# SparkFun_ESP8266_Thing_V10a.net
KiCad netlist of a schematic drawn in EAGLE
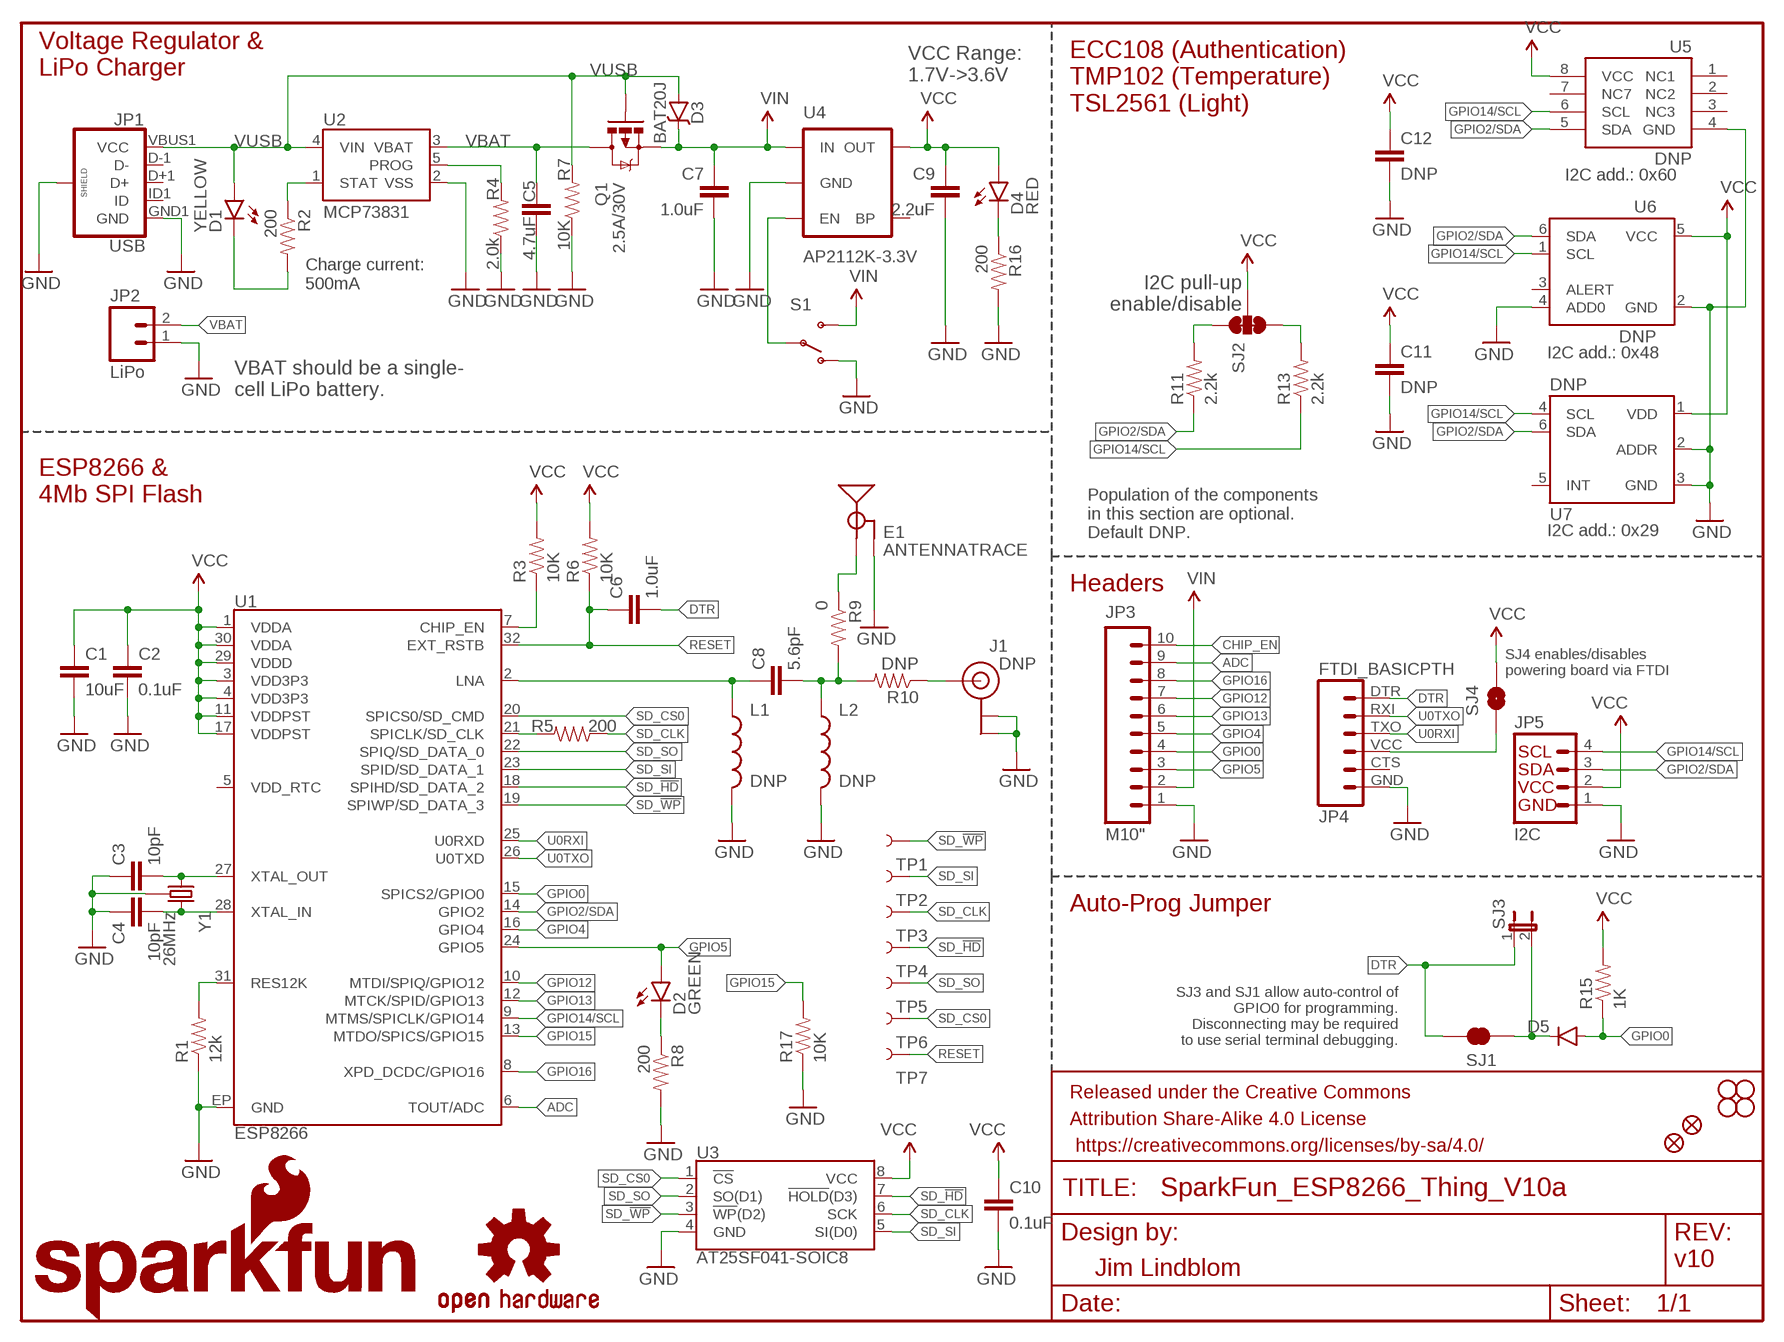
[diagram p0: schematic, sheet 1]

(export (version "E")
  (design (tool "Eeschema 10.0.6"))
  (components
    (comp (ref "C1")
      (value "10uF")
      (footprint "eagle-import:0603-CAP")
      (libsource (lib "eagle-import") (part "10UF-6.3V-20%(0603)"))
    )
    (comp (ref "C2")
      (value "0.1uF")
      (footprint "eagle-import:0603-CAP")
      (libsource (lib "eagle-import") (part "0.1UF-25V(+80/-20%)(0603)"))
    )
    (comp (ref "C3")
      (value "10pF")
      (footprint "eagle-import:0603-CAP")
      (libsource (lib "eagle-import") (part "10PF-50V-5%(0603)"))
    )
    (comp (ref "C4")
      (value "10pF")
      (footprint "eagle-import:0603-CAP")
      (libsource (lib "eagle-import") (part "10PF-50V-5%(0603)"))
    )
    (comp (ref "C5")
      (value "4.7uF")
      (footprint "eagle-import:0603-CAP")
      (libsource (lib "eagle-import") (part "4.7UF-6.3V-10%(0603)0603"))
    )
    (comp (ref "C6")
      (value "1.0uF")
      (footprint "eagle-import:0603-CAP")
      (libsource (lib "eagle-import") (part "1.0UF-16V-10%(0603)"))
    )
    (comp (ref "C7")
      (value "1.0uF")
      (footprint "eagle-import:0805")
      (libsource (lib "eagle-import") (part "1.0UF-25V-+80/-20(0805)"))
    )
    (comp (ref "C8")
      (value "5.6pF")
      (footprint "eagle-import:0603-CAP")
      (libsource (lib "eagle-import") (part "CAP0603-CAP"))
    )
    (comp (ref "C9")
      (value "2.2uF")
      (footprint "eagle-import:0603-CAP")
      (libsource (lib "eagle-import") (part "2.2UF-10V-20%(0603)"))
    )
    (comp (ref "C10")
      (value "0.1uF")
      (footprint "eagle-import:0603-CAP")
      (libsource (lib "eagle-import") (part "0.1UF-25V(+80/-20%)(0603)"))
    )
    (comp (ref "C11")
      (value "DNP")
      (footprint "eagle-import:0603-CAP")
      (libsource (lib "eagle-import") (part "0.1UF-25V(+80/-20%)(0603)"))
    )
    (comp (ref "C12")
      (value "DNP")
      (footprint "eagle-import:0603-CAP")
      (libsource (lib "eagle-import") (part "0.1UF-25V(+80/-20%)(0603)"))
    )
    (comp (ref "D1")
      (value "YELLOW")
      (footprint "eagle-import:LED-0603")
      (libsource (lib "eagle-import") (part "LED-YELLOW0603"))
    )
    (comp (ref "D2")
      (value "GREEN")
      (footprint "eagle-import:LED-0603")
      (libsource (lib "eagle-import") (part "LED-GREEN0603"))
    )
    (comp (ref "D3")
      (value "BAT20J")
      (footprint "eagle-import:SOD-323")
      (libsource (lib "eagle-import") (part "DIODE-SCHOTTKY-BAT20J"))
    )
    (comp (ref "D4")
      (value "RED")
      (footprint "eagle-import:LED-0603")
      (libsource (lib "eagle-import") (part "LED-RED0603"))
    )
    (comp (ref "D5")
      (value "DIODEBAS16")
      (footprint "eagle-import:SOD-323")
      (libsource (lib "eagle-import") (part "DIODEBAS16"))
    )
    (comp (ref "E1")
      (value "ANTENNATRACE")
      (footprint "eagle-import:TRACE_ANTENNA_2.4GHZ_25.7MM")
      (libsource (lib "eagle-import") (part "ANTENNATRACE"))
    )
    (comp (ref "FID1")
      (value "FIDUCIAL1X2")
      (footprint "eagle-import:FIDUCIAL-1X2")
      (libsource (lib "eagle-import") (part "FIDUCIAL1X2"))
    )
    (comp (ref "FID2")
      (value "FIDUCIAL1X2")
      (footprint "eagle-import:FIDUCIAL-1X2")
      (libsource (lib "eagle-import") (part "FIDUCIAL1X2"))
    )
    (comp (ref "FRAME1")
      (value "FRAME-LETTER")
      (footprint "eagle-import:CREATIVE_COMMONS")
      (libsource (lib "eagle-import") (part "FRAME-LETTER"))
    )
    (comp (ref "J1")
      (value "DNP")
      (footprint "eagle-import:U.FL")
      (libsource (lib "eagle-import") (part "U.FL"))
    )
    (comp (ref "JP1")
      (value "USB")
      (footprint "eagle-import:USB-B-MICRO-SMD_V03")
      (libsource (lib "eagle-import") (part "USB_MICROB_PLUGCONN-11752"))
    )
    (comp (ref "JP2")
      (value "LiPo")
      (footprint "eagle-import:JST-2-PTH")
      (libsource (lib "eagle-import") (part "M02JST-PTH-2"))
    )
    (comp (ref "JP3")
      (value "M10\"")
      (footprint "eagle-import:1X10")
      (libsource (lib "eagle-import") (part "M10{dblquote}"))
    )
    (comp (ref "JP4")
      (value "FTDI_BASICPTH")
      (footprint "eagle-import:FTDI_BASIC")
      (libsource (lib "eagle-import") (part "FTDI_BASICPTH"))
    )
    (comp (ref "JP5")
      (value "I2C")
      (footprint "eagle-import:1X04")
      (libsource (lib "eagle-import") (part "I2C_STANDARD"))
    )
    (comp (ref "L1")
      (value "DNP")
      (footprint "eagle-import:0603")
      (libsource (lib "eagle-import") (part "INDUCTOR0603"))
    )
    (comp (ref "L2")
      (value "DNP")
      (footprint "eagle-import:0603")
      (libsource (lib "eagle-import") (part "INDUCTOR0603"))
    )
    (comp (ref "LOGO1")
      (value "SFE_LOGO_NAME.2_INCH")
      (footprint "eagle-import:SFE_LOGO_NAME_.2")
      (libsource (lib "eagle-import") (part "SFE_LOGO_NAME.2_INCH"))
    )
    (comp (ref "LOGO3")
      (value "SFE_LOGO_FLAME.1_INCH")
      (footprint "eagle-import:SFE_LOGO_FLAME_.1")
      (libsource (lib "eagle-import") (part "SFE_LOGO_FLAME.1_INCH"))
    )
    (comp (ref "LOGO4")
      (value "OSHW-LOGOS")
      (footprint "eagle-import:OSHW-LOGO-S")
      (libsource (lib "eagle-import") (part "OSHW-LOGOS"))
    )
    (comp (ref "Q1")
      (value "2.5A/30V")
      (footprint "eagle-import:SOT23-3")
      (libsource (lib "eagle-import") (part "MOSFET-PCHANNELDMG2307L"))
    )
    (comp (ref "R1")
      (value "12k")
      (footprint "eagle-import:0603-RES")
      (libsource (lib "eagle-import") (part "12KOHM-1/10W-1%(0603)"))
    )
    (comp (ref "R2")
      (value "200")
      (footprint "eagle-import:0603-RES")
      (libsource (lib "eagle-import") (part "200OHM1/10W1%(0603)"))
    )
    (comp (ref "R3")
      (value "10K")
      (footprint "eagle-import:0603-RES")
      (libsource (lib "eagle-import") (part "10KOHM1/10W1%(0603)0603"))
    )
    (comp (ref "R4")
      (value "2.0k")
      (footprint "eagle-import:0603-RES")
      (libsource (lib "eagle-import") (part "2.0KOHM1/10W5%(0603)"))
    )
    (comp (ref "R5")
      (value "200")
      (footprint "eagle-import:0603-RES")
      (libsource (lib "eagle-import") (part "200OHM1/10W1%(0603)"))
    )
    (comp (ref "R6")
      (value "10K")
      (footprint "eagle-import:0603-RES")
      (libsource (lib "eagle-import") (part "10KOHM1/10W1%(0603)0603"))
    )
    (comp (ref "R7")
      (value "10K")
      (footprint "eagle-import:0603-RES")
      (libsource (lib "eagle-import") (part "10KOHM1/10W1%(0603)0603"))
    )
    (comp (ref "R8")
      (value "200")
      (footprint "eagle-import:0603-RES")
      (libsource (lib "eagle-import") (part "200OHM1/10W1%(0603)"))
    )
    (comp (ref "R9")
      (value "0")
      (footprint "eagle-import:0603")
      (libsource (lib "eagle-import") (part "0OHM1/10W5%(0603)"))
    )
    (comp (ref "R10")
      (value "DNP")
      (footprint "eagle-import:0603-RES")
      (libsource (lib "eagle-import") (part "RESISTOR0603-RES"))
    )
    (comp (ref "R11")
      (value "2.2k")
      (footprint "eagle-import:0603-RES")
      (libsource (lib "eagle-import") (part "2.2KOHM1/10W1%(0603)"))
    )
    (comp (ref "R13")
      (value "2.2k")
      (footprint "eagle-import:0603-RES")
      (libsource (lib "eagle-import") (part "2.2KOHM1/10W1%(0603)"))
    )
    (comp (ref "R15")
      (value "1K")
      (footprint "eagle-import:0603-RES")
      (libsource (lib "eagle-import") (part "1KOHM1/10W1%(0603)"))
    )
    (comp (ref "R16")
      (value "200")
      (footprint "eagle-import:0603-RES")
      (libsource (lib "eagle-import") (part "200OHM1/10W1%(0603)"))
    )
    (comp (ref "R17")
      (value "10K")
      (footprint "eagle-import:0603-RES")
      (libsource (lib "eagle-import") (part "10KOHM1/10W1%(0603)0603"))
    )
    (comp (ref "S1")
      (value "SWITCH-SPDT-SMD-A")
      (footprint "eagle-import:SWITCH-SPST-SMD-A")
      (libsource (lib "eagle-import") (part "SWITCH-SPDT-SMD-A"))
    )
    (comp (ref "SJ1")
      (value "JUMPER-PAD-2-NC_BY_TRACE")
      (footprint "eagle-import:PAD-JUMPER-2-NC_BY_TRACE_YES_SILK")
      (libsource (lib "eagle-import") (part "JUMPER-PAD-2-NC_BY_TRACE"))
    )
    (comp (ref "SJ2")
      (value "JUMPER-PAD-3-NC_BY_TRACE")
      (footprint "eagle-import:PAD-JUMPER-3-3OF3_NC_BY_TRACE_YES_SILK_FULL_BOX")
      (libsource (lib "eagle-import") (part "JUMPER-PAD-3-NC_BY_TRACE"))
    )
    (comp (ref "SJ3")
      (value "JUMPER-PTH-2-NC")
      (footprint "eagle-import:PTH-JUMPER-NC_BOTTOM_NO_SILK")
      (libsource (lib "eagle-import") (part "JUMPER-PTH-2-NC"))
    )
    (comp (ref "SJ4")
      (value "JUMPER-PAD-2-NOYES_SILK")
      (footprint "eagle-import:PAD-JUMPER-2-NO_YES_SILK")
      (libsource (lib "eagle-import") (part "JUMPER-PAD-2-NOYES_SILK"))
    )
    (comp (ref "STANDOFF1")
      (value "STAND-OFF")
      (footprint "eagle-import:STAND-OFF")
      (libsource (lib "eagle-import") (part "STAND-OFF"))
    )
    (comp (ref "STANDOFF2")
      (value "STAND-OFF")
      (footprint "eagle-import:STAND-OFF")
      (libsource (lib "eagle-import") (part "STAND-OFF"))
    )
    (comp (ref "STANDOFF3")
      (value "STAND-OFF")
      (footprint "eagle-import:STAND-OFF")
      (libsource (lib "eagle-import") (part "STAND-OFF"))
    )
    (comp (ref "STANDOFF4")
      (value "STAND-OFF")
      (footprint "eagle-import:STAND-OFF")
      (libsource (lib "eagle-import") (part "STAND-OFF"))
    )
    (comp (ref "TP1")
      (value "TEST-POINT3X5")
      (footprint "eagle-import:PAD.03X.05")
      (libsource (lib "eagle-import") (part "TEST-POINT3X5"))
    )
    (comp (ref "TP2")
      (value "TEST-POINT3X5")
      (footprint "eagle-import:PAD.03X.05")
      (libsource (lib "eagle-import") (part "TEST-POINT3X5"))
    )
    (comp (ref "TP3")
      (value "TEST-POINT3X5")
      (footprint "eagle-import:PAD.03X.05")
      (libsource (lib "eagle-import") (part "TEST-POINT3X5"))
    )
    (comp (ref "TP4")
      (value "TEST-POINT3X5")
      (footprint "eagle-import:PAD.03X.05")
      (libsource (lib "eagle-import") (part "TEST-POINT3X5"))
    )
    (comp (ref "TP5")
      (value "TEST-POINT3X5")
      (footprint "eagle-import:PAD.03X.05")
      (libsource (lib "eagle-import") (part "TEST-POINT3X5"))
    )
    (comp (ref "TP6")
      (value "TEST-POINT3X5")
      (footprint "eagle-import:PAD.03X.05")
      (libsource (lib "eagle-import") (part "TEST-POINT3X5"))
    )
    (comp (ref "TP7")
      (value "TEST-POINT3X5")
      (footprint "eagle-import:PAD.03X.05")
      (libsource (lib "eagle-import") (part "TEST-POINT3X5"))
    )
    (comp (ref "U1")
      (value "ESP8266")
      (footprint "eagle-import:QFN32")
      (libsource (lib "eagle-import") (part "ESP8266"))
    )
    (comp (ref "U2")
      (value "MCP73831")
      (footprint "eagle-import:SOT23-5")
      (libsource (lib "eagle-import") (part "MCP73831"))
    )
    (comp (ref "U3")
      (value "AT25SF041-SOIC8")
      (footprint "eagle-import:SO08")
      (libsource (lib "eagle-import") (part "AT25SF041-SOIC8"))
    )
    (comp (ref "U4")
      (value "AP2112K-3.3V")
      (footprint "eagle-import:SOT23-5")
      (libsource (lib "eagle-import") (part "V_REG_LDOSMD"))
    )
    (comp (ref "U5")
      (value "DNP")
      (footprint "eagle-import:UDFN8")
      (libsource (lib "eagle-import") (part "ATECC108-MAHDA"))
    )
    (comp (ref "U6")
      (value "DNP")
      (footprint "eagle-import:SOT563-2")
      (libsource (lib "eagle-import") (part "TMP1021{colon}1"))
    )
    (comp (ref "U7")
      (value "DNP")
      (footprint "eagle-import:FN-6")
      (libsource (lib "eagle-import") (part "TSL2561FN"))
    )
    (comp (ref "Y1")
      (value "26MHz")
      (footprint "eagle-import:CRYSTAL-SMD-3.2X2.5")
      (libsource (lib "eagle-import") (part "CRYSTAL-GROUNDED3.2X2.5"))
    )
  )
  (nets
    (net (code "1") (name "/SD_~{HD}") (class "Default")
      (node (ref "TP4") (pin "P$1") (pinfunction "1_P$1") (pintype "bidirectional"))
      (node (ref "U1") (pin "18") (pinfunction "SPIHD/SD_DATA_2_18") (pintype "bidirectional"))
      (node (ref "U3") (pin "7") (pinfunction "~{HOLD}(D3)_7") (pintype "bidirectional"))
    )
    (net (code "2") (name "/SD_~{WP}") (class "Default")
      (node (ref "TP1") (pin "P$1") (pinfunction "1_P$1") (pintype "bidirectional"))
      (node (ref "U1") (pin "19") (pinfunction "SPIWP/SD_DATA_3_19") (pintype "bidirectional"))
      (node (ref "U3") (pin "3") (pinfunction "~{WP}(D2)_3") (pintype "bidirectional"))
    )
    (net (code "3") (name "/VUSB") (class "Default")
      (node (ref "D1") (pin "A") (pinfunction "A_A") (pintype "passive"))
      (node (ref "D3") (pin "A") (pinfunction "A_A") (pintype "passive"))
      (node (ref "JP1") (pin "VBUS1") (pinfunction "VCC_VBUS1") (pintype "bidirectional"))
      (node (ref "Q1") (pin "1") (pinfunction "G_1") (pintype "passive"))
      (node (ref "R7") (pin "2") (pinfunction "2_2") (pintype "passive"))
      (node (ref "U2") (pin "4") (pinfunction "VIN_4") (pintype "power_in"))
    )
    (net (code "4") (name "ADC") (class "Default")
      (node (ref "JP3") (pin "9") (pinfunction "9_9") (pintype "passive"))
      (node (ref "U1") (pin "6") (pinfunction "TOUT/ADC_6") (pintype "bidirectional"))
    )
    (net (code "5") (name "CHIP_EN") (class "Default")
      (node (ref "JP3") (pin "10") (pinfunction "10_10") (pintype "passive"))
      (node (ref "R3") (pin "1") (pinfunction "1_1") (pintype "passive"))
      (node (ref "U1") (pin "7") (pinfunction "CHIP_EN_7") (pintype "bidirectional"))
    )
    (net (code "6") (name "DTR") (class "Default")
      (node (ref "C6") (pin "2") (pinfunction "2_2") (pintype "passive"))
      (node (ref "JP4") (pin "DTR") (pinfunction "1_DTR") (pintype "passive"))
      (node (ref "SJ1") (pin "2") (pinfunction "2_2") (pintype "passive"))
      (node (ref "SJ3") (pin "1") (pinfunction "1_1") (pintype "passive"))
    )
    (net (code "7") (name "GND") (class "Default")
      (node (ref "C1") (pin "2") (pinfunction "2_2") (pintype "passive"))
      (node (ref "C10") (pin "2") (pinfunction "2_2") (pintype "passive"))
      (node (ref "C11") (pin "2") (pinfunction "2_2") (pintype "passive"))
      (node (ref "C12") (pin "2") (pinfunction "2_2") (pintype "passive"))
      (node (ref "C2") (pin "2") (pinfunction "2_2") (pintype "passive"))
      (node (ref "C3") (pin "1") (pinfunction "1_1") (pintype "passive"))
      (node (ref "C4") (pin "1") (pinfunction "1_1") (pintype "passive"))
      (node (ref "C5") (pin "2") (pinfunction "2_2") (pintype "passive"))
      (node (ref "C7") (pin "2") (pinfunction "2_2") (pintype "passive"))
      (node (ref "C9") (pin "2") (pinfunction "2_2") (pintype "passive"))
      (node (ref "E1") (pin "GND") (pinfunction "GND_GND") (pintype "bidirectional"))
      (node (ref "E1") (pin "GND2") (pinfunction "GND_GND2") (pintype "bidirectional"))
      (node (ref "J1") (pin "P$1") (pinfunction "GND_P$1") (pintype "bidirectional"))
      (node (ref "J1") (pin "P$2") (pinfunction "GND_P$2") (pintype "bidirectional"))
      (node (ref "JP1") (pin "GND1") (pinfunction "GND_GND1") (pintype "bidirectional"))
      (node (ref "JP1") (pin "SHIELD1") (pinfunction "SHIELD_SHIELD1") (pintype "bidirectional"))
      (node (ref "JP1") (pin "SHIELD2") (pinfunction "SHIELD_SHIELD2") (pintype "bidirectional"))
      (node (ref "JP1") (pin "SHIELD3") (pinfunction "SHIELD_SHIELD3") (pintype "bidirectional"))
      (node (ref "JP2") (pin "1") (pinfunction "1_1") (pintype "passive"))
      (node (ref "JP3") (pin "1") (pinfunction "1_1") (pintype "passive"))
      (node (ref "JP4") (pin "GND") (pinfunction "6_GND") (pintype "passive"))
      (node (ref "JP5") (pin "1") (pinfunction "1_1") (pintype "passive"))
      (node (ref "L1") (pin "2") (pinfunction "2_2") (pintype "passive"))
      (node (ref "L2") (pin "2") (pinfunction "2_2") (pintype "passive"))
      (node (ref "R1") (pin "1") (pinfunction "1_1") (pintype "passive"))
      (node (ref "R16") (pin "2") (pinfunction "2_2") (pintype "passive"))
      (node (ref "R17") (pin "1") (pinfunction "1_1") (pintype "passive"))
      (node (ref "R4") (pin "1") (pinfunction "1_1") (pintype "passive"))
      (node (ref "R7") (pin "1") (pinfunction "1_1") (pintype "passive"))
      (node (ref "R8") (pin "2") (pinfunction "2_2") (pintype "passive"))
      (node (ref "S1") (pin "1") (pinfunction "O_1") (pintype "passive"))
      (node (ref "U1") (pin "EP") (pinfunction "GND_EP") (pintype "bidirectional"))
      (node (ref "U2") (pin "2") (pinfunction "VSS_2") (pintype "power_in"))
      (node (ref "U3") (pin "4") (pinfunction "GND_4") (pintype "bidirectional"))
      (node (ref "U4") (pin "2") (pinfunction "GND_2") (pintype "input"))
      (node (ref "U5") (pin "4") (pinfunction "GND_4") (pintype "power_in"))
      (node (ref "U6") (pin "2") (pinfunction "GND_2") (pintype "bidirectional"))
      (node (ref "U6") (pin "4") (pinfunction "ADD0_4") (pintype "bidirectional"))
      (node (ref "U7") (pin "2") (pinfunction "ADDR_2") (pintype "input"))
      (node (ref "U7") (pin "3") (pinfunction "GND_3") (pintype "power_in"))
      (node (ref "Y1") (pin "2") (pinfunction "GND_2") (pintype "passive"))
      (node (ref "Y1") (pin "4") (pinfunction "GND_4") (pintype "passive"))
    )
    (net (code "8") (name "GPIO0") (class "Default")
      (node (ref "D5") (pin "A") (pinfunction "A_A") (pintype "passive"))
      (node (ref "JP3") (pin "4") (pinfunction "4_4") (pintype "passive"))
      (node (ref "R15") (pin "1") (pinfunction "1_1") (pintype "passive"))
      (node (ref "U1") (pin "15") (pinfunction "SPICS2/GPIO0_15") (pintype "bidirectional"))
    )
    (net (code "9") (name "GPIO2{slash}SDA") (class "Default")
      (node (ref "JP5") (pin "3") (pinfunction "3_3") (pintype "passive"))
      (node (ref "R11") (pin "1") (pinfunction "1_1") (pintype "passive"))
      (node (ref "U1") (pin "14") (pinfunction "GPIO2_14") (pintype "bidirectional"))
      (node (ref "U5") (pin "5") (pinfunction "SDA_5") (pintype "bidirectional"))
      (node (ref "U6") (pin "6") (pinfunction "SDA_6") (pintype "bidirectional"))
      (node (ref "U7") (pin "6") (pinfunction "SDA_6") (pintype "bidirectional"))
    )
    (net (code "10") (name "GPIO4") (class "Default")
      (node (ref "JP3") (pin "5") (pinfunction "5_5") (pintype "passive"))
      (node (ref "U1") (pin "16") (pinfunction "GPIO4_16") (pintype "bidirectional"))
    )
    (net (code "11") (name "GPIO5") (class "Default")
      (node (ref "D2") (pin "A") (pinfunction "A_A") (pintype "passive"))
      (node (ref "JP3") (pin "3") (pinfunction "3_3") (pintype "passive"))
      (node (ref "U1") (pin "24") (pinfunction "GPIO5_24") (pintype "bidirectional"))
    )
    (net (code "12") (name "GPIO12") (class "Default")
      (node (ref "JP3") (pin "7") (pinfunction "7_7") (pintype "passive"))
      (node (ref "U1") (pin "10") (pinfunction "MTDI/SPIQ/GPIO12_10") (pintype "bidirectional"))
    )
    (net (code "13") (name "GPIO13") (class "Default")
      (node (ref "JP3") (pin "6") (pinfunction "6_6") (pintype "passive"))
      (node (ref "U1") (pin "12") (pinfunction "MTCK/SPID/GPIO13_12") (pintype "bidirectional"))
    )
    (net (code "14") (name "GPIO14{slash}SCL") (class "Default")
      (node (ref "JP5") (pin "4") (pinfunction "4_4") (pintype "passive"))
      (node (ref "R13") (pin "1") (pinfunction "1_1") (pintype "passive"))
      (node (ref "U1") (pin "9") (pinfunction "MTMS/SPICLK/GPIO14_9") (pintype "bidirectional"))
      (node (ref "U5") (pin "6") (pinfunction "SCL_6") (pintype "bidirectional"))
      (node (ref "U6") (pin "1") (pinfunction "SCL_1") (pintype "bidirectional"))
      (node (ref "U7") (pin "4") (pinfunction "SCL_4") (pintype "input"))
    )
    (net (code "15") (name "GPIO15") (class "Default")
      (node (ref "R17") (pin "2") (pinfunction "2_2") (pintype "passive"))
      (node (ref "U1") (pin "13") (pinfunction "MTDO/SPICS/GPIO15_13") (pintype "bidirectional"))
    )
    (net (code "16") (name "GPIO16") (class "Default")
      (node (ref "JP3") (pin "8") (pinfunction "8_8") (pintype "passive"))
      (node (ref "U1") (pin "8") (pinfunction "XPD_DCDC/GPIO16_8") (pintype "bidirectional"))
    )
    (net (code "17") (name "Net-(C8-Pad2)") (class "Default")
      (node (ref "C8") (pin "2") (pinfunction "2_2") (pintype "passive"))
      (node (ref "L2") (pin "1") (pinfunction "1_1") (pintype "passive"))
      (node (ref "R10") (pin "2") (pinfunction "2_2") (pintype "passive"))
      (node (ref "R9") (pin "2") (pinfunction "2_2") (pintype "passive"))
    )
    (net (code "18") (name "Net-(D1-PadC)") (class "Default")
      (node (ref "D1") (pin "C") (pinfunction "C_C") (pintype "passive"))
      (node (ref "R2") (pin "2") (pinfunction "2_2") (pintype "passive"))
    )
    (net (code "19") (name "Net-(D2-PadC)") (class "Default")
      (node (ref "D2") (pin "C") (pinfunction "C_C") (pintype "passive"))
      (node (ref "R8") (pin "1") (pinfunction "1_1") (pintype "passive"))
    )
    (net (code "20") (name "Net-(D4-PadC)") (class "Default")
      (node (ref "D4") (pin "C") (pinfunction "C_C") (pintype "passive"))
      (node (ref "R16") (pin "1") (pinfunction "1_1") (pintype "passive"))
    )
    (net (code "21") (name "Net-(D5-PadC)") (class "Default")
      (node (ref "D5") (pin "C") (pinfunction "C_C") (pintype "passive"))
      (node (ref "SJ1") (pin "1") (pinfunction "1_1") (pintype "passive"))
      (node (ref "SJ3") (pin "2") (pinfunction "2_2") (pintype "passive"))
    )
    (net (code "22") (name "Net-(E1-SIGNAL)") (class "Default")
      (node (ref "E1") (pin "ANT") (pinfunction "SIGNAL_ANT") (pintype "bidirectional"))
      (node (ref "R9") (pin "1") (pinfunction "1_1") (pintype "passive"))
    )
    (net (code "23") (name "Net-(J1-SIGNAL)") (class "Default")
      (node (ref "J1") (pin "P$3") (pinfunction "SIGNAL_P$3") (pintype "bidirectional"))
      (node (ref "R10") (pin "1") (pinfunction "1_1") (pintype "passive"))
    )
    (net (code "24") (name "Net-(JP4-4)") (class "Default")
      (node (ref "JP4") (pin "VCC") (pinfunction "4_VCC") (pintype "passive"))
      (node (ref "SJ4") (pin "1") (pinfunction "1_1") (pintype "passive"))
    )
    (net (code "25") (name "Net-(R11-Pad2)") (class "Default")
      (node (ref "R11") (pin "2") (pinfunction "2_2") (pintype "passive"))
      (node (ref "SJ2") (pin "1") (pinfunction "1_1") (pintype "passive"))
    )
    (net (code "26") (name "Net-(R13-Pad2)") (class "Default")
      (node (ref "R13") (pin "2") (pinfunction "2_2") (pintype "passive"))
      (node (ref "SJ2") (pin "3") (pinfunction "3_3") (pintype "passive"))
    )
    (net (code "27") (name "Net-(S1-P)") (class "Default")
      (node (ref "S1") (pin "2") (pinfunction "P_2") (pintype "passive"))
      (node (ref "U4") (pin "3") (pinfunction "EN_3") (pintype "input"))
    )
    (net (code "28") (name "Net-(U1-LNA)") (class "Default")
      (node (ref "C8") (pin "1") (pinfunction "1_1") (pintype "passive"))
      (node (ref "L1") (pin "1") (pinfunction "1_1") (pintype "passive"))
      (node (ref "U1") (pin "2") (pinfunction "LNA_2") (pintype "bidirectional"))
    )
    (net (code "29") (name "Net-(U1-RES12K)") (class "Default")
      (node (ref "R1") (pin "2") (pinfunction "2_2") (pintype "passive"))
      (node (ref "U1") (pin "31") (pinfunction "RES12K_31") (pintype "bidirectional"))
    )
    (net (code "30") (name "Net-(U1-SPICLK{slash}SD_CLK)") (class "Default")
      (node (ref "R5") (pin "2") (pinfunction "2_2") (pintype "passive"))
      (node (ref "U1") (pin "21") (pinfunction "SPICLK/SD_CLK_21") (pintype "bidirectional"))
    )
    (net (code "31") (name "Net-(U1-XTAL_IN)") (class "Default")
      (node (ref "C4") (pin "2") (pinfunction "2_2") (pintype "passive"))
      (node (ref "U1") (pin "28") (pinfunction "XTAL_IN_28") (pintype "bidirectional"))
      (node (ref "Y1") (pin "3") (pinfunction "2_3") (pintype "passive"))
    )
    (net (code "32") (name "Net-(U1-XTAL_OUT)") (class "Default")
      (node (ref "C3") (pin "2") (pinfunction "2_2") (pintype "passive"))
      (node (ref "U1") (pin "27") (pinfunction "XTAL_OUT_27") (pintype "bidirectional"))
      (node (ref "Y1") (pin "1") (pinfunction "1_1") (pintype "passive"))
    )
    (net (code "33") (name "Net-(U2-PROG)") (class "Default")
      (node (ref "R4") (pin "2") (pinfunction "2_2") (pintype "passive"))
      (node (ref "U2") (pin "5") (pinfunction "PROG_5") (pintype "input"))
    )
    (net (code "34") (name "Net-(U2-STAT)") (class "Default")
      (node (ref "R2") (pin "1") (pinfunction "1_1") (pintype "passive"))
      (node (ref "U2") (pin "1") (pinfunction "STAT_1") (pintype "output"))
    )
    (net (code "35") (name "RESET") (class "Default")
      (node (ref "C6") (pin "1") (pinfunction "1_1") (pintype "passive"))
      (node (ref "R6") (pin "1") (pinfunction "1_1") (pintype "passive"))
      (node (ref "TP7") (pin "P$1") (pinfunction "1_P$1") (pintype "bidirectional"))
      (node (ref "U1") (pin "32") (pinfunction "EXT_RSTB_32") (pintype "bidirectional"))
    )
    (net (code "36") (name "SD_CLK") (class "Default")
      (node (ref "R5") (pin "1") (pinfunction "1_1") (pintype "passive"))
      (node (ref "TP3") (pin "P$1") (pinfunction "1_P$1") (pintype "bidirectional"))
      (node (ref "U3") (pin "6") (pinfunction "SCK_6") (pintype "bidirectional"))
    )
    (net (code "37") (name "SD_CS0") (class "Default")
      (node (ref "TP6") (pin "P$1") (pinfunction "1_P$1") (pintype "bidirectional"))
      (node (ref "U1") (pin "20") (pinfunction "SPICS0/SD_CMD_20") (pintype "bidirectional"))
      (node (ref "U3") (pin "1") (pinfunction "~{CS}_1") (pintype "bidirectional"))
    )
    (net (code "38") (name "SD_SI") (class "Default")
      (node (ref "TP2") (pin "P$1") (pinfunction "1_P$1") (pintype "bidirectional"))
      (node (ref "U1") (pin "23") (pinfunction "SPID/SD_DATA_1_23") (pintype "bidirectional"))
      (node (ref "U3") (pin "5") (pinfunction "SI(D0)_5") (pintype "bidirectional"))
    )
    (net (code "39") (name "SD_SO") (class "Default")
      (node (ref "TP5") (pin "P$1") (pinfunction "1_P$1") (pintype "bidirectional"))
      (node (ref "U1") (pin "22") (pinfunction "SPIQ/SD_DATA_0_22") (pintype "bidirectional"))
      (node (ref "U3") (pin "2") (pinfunction "SO(D1)_2") (pintype "bidirectional"))
    )
    (net (code "40") (name "U0RXI") (class "Default")
      (node (ref "JP4") (pin "TXO") (pinfunction "3_TXO") (pintype "passive"))
      (node (ref "U1") (pin "25") (pinfunction "U0RXD_25") (pintype "bidirectional"))
    )
    (net (code "41") (name "U0TXO") (class "Default")
      (node (ref "JP4") (pin "RXI") (pinfunction "2_RXI") (pintype "passive"))
      (node (ref "U1") (pin "26") (pinfunction "U0TXD_26") (pintype "bidirectional"))
    )
    (net (code "42") (name "VBAT") (class "Default")
      (node (ref "C5") (pin "1") (pinfunction "1_1") (pintype "passive"))
      (node (ref "JP2") (pin "2") (pinfunction "2_2") (pintype "passive"))
      (node (ref "Q1") (pin "3") (pinfunction "D_3") (pintype "passive"))
      (node (ref "U2") (pin "3") (pinfunction "VBAT_3") (pintype "power_in"))
    )
    (net (code "43") (name "VCC") (class "Default")
      (node (ref "C1") (pin "1") (pinfunction "1_1") (pintype "passive"))
      (node (ref "C10") (pin "1") (pinfunction "1_1") (pintype "passive"))
      (node (ref "C11") (pin "1") (pinfunction "1_1") (pintype "passive"))
      (node (ref "C12") (pin "1") (pinfunction "1_1") (pintype "passive"))
      (node (ref "C2") (pin "1") (pinfunction "1_1") (pintype "passive"))
      (node (ref "C9") (pin "1") (pinfunction "1_1") (pintype "passive"))
      (node (ref "D4") (pin "A") (pinfunction "A_A") (pintype "passive"))
      (node (ref "JP5") (pin "2") (pinfunction "2_2") (pintype "passive"))
      (node (ref "R15") (pin "2") (pinfunction "2_2") (pintype "passive"))
      (node (ref "R3") (pin "2") (pinfunction "2_2") (pintype "passive"))
      (node (ref "R6") (pin "2") (pinfunction "2_2") (pintype "passive"))
      (node (ref "SJ2") (pin "2") (pinfunction "2_2") (pintype "passive"))
      (node (ref "SJ4") (pin "2") (pinfunction "2_2") (pintype "passive"))
      (node (ref "U1") (pin "1") (pinfunction "VDDA_1") (pintype "bidirectional"))
      (node (ref "U1") (pin "11") (pinfunction "VDDPST_11") (pintype "bidirectional"))
      (node (ref "U1") (pin "17") (pinfunction "VDDPST_17") (pintype "bidirectional"))
      (node (ref "U1") (pin "29") (pinfunction "VDDD_29") (pintype "bidirectional"))
      (node (ref "U1") (pin "3") (pinfunction "VDD3P3_3") (pintype "bidirectional"))
      (node (ref "U1") (pin "30") (pinfunction "VDDA_30") (pintype "bidirectional"))
      (node (ref "U1") (pin "4") (pinfunction "VDD3P3_4") (pintype "bidirectional"))
      (node (ref "U3") (pin "8") (pinfunction "VCC_8") (pintype "bidirectional"))
      (node (ref "U4") (pin "5") (pinfunction "OUT_5") (pintype "passive"))
      (node (ref "U5") (pin "8") (pinfunction "VCC_8") (pintype "power_in"))
      (node (ref "U6") (pin "5") (pinfunction "VCC_5") (pintype "bidirectional"))
      (node (ref "U7") (pin "1") (pinfunction "VDD_1") (pintype "power_in"))
    )
    (net (code "44") (name "VIN") (class "Default")
      (node (ref "C7") (pin "1") (pinfunction "1_1") (pintype "passive"))
      (node (ref "D3") (pin "C") (pinfunction "C_C") (pintype "passive"))
      (node (ref "JP3") (pin "2") (pinfunction "2_2") (pintype "passive"))
      (node (ref "Q1") (pin "2") (pinfunction "S_2") (pintype "passive"))
      (node (ref "S1") (pin "3") (pinfunction "S_3") (pintype "passive"))
      (node (ref "U4") (pin "1") (pinfunction "IN_1") (pintype "input"))
    )
    (net (code "45") (name "unconnected-(JP1-D+-PadD+1)") (class "Default")
      (node (ref "JP1") (pin "D+1") (pinfunction "D+_D+1") (pintype "bidirectional"))
    )
    (net (code "46") (name "unconnected-(JP1-D--PadD-1)") (class "Default")
      (node (ref "JP1") (pin "D-1") (pinfunction "D-_D-1") (pintype "bidirectional"))
    )
    (net (code "47") (name "unconnected-(JP1-ID-PadID1)") (class "Default")
      (node (ref "JP1") (pin "ID1") (pinfunction "ID_ID1") (pintype "bidirectional"))
    )
    (net (code "48") (name "unconnected-(JP4-5-PadCTS)") (class "Default")
      (node (ref "JP4") (pin "CTS") (pinfunction "5_CTS") (pintype "passive"))
    )
    (net (code "49") (name "unconnected-(U1-VDD_RTC-Pad5)") (class "Default")
      (node (ref "U1") (pin "5") (pinfunction "VDD_RTC_5") (pintype "bidirectional"))
    )
    (net (code "50") (name "unconnected-(U4-BP-Pad4)") (class "Default")
      (node (ref "U4") (pin "4") (pinfunction "BP_4") (pintype "input"))
    )
    (net (code "51") (name "unconnected-(U5-NC1-Pad1)") (class "Default")
      (node (ref "U5") (pin "1") (pinfunction "NC1_1") (pintype "bidirectional"))
    )
    (net (code "52") (name "unconnected-(U5-NC2-Pad2)") (class "Default")
      (node (ref "U5") (pin "2") (pinfunction "NC2_2") (pintype "no_connect"))
    )
    (net (code "53") (name "unconnected-(U5-NC3-Pad3)") (class "Default")
      (node (ref "U5") (pin "3") (pinfunction "NC3_3") (pintype "no_connect"))
    )
    (net (code "54") (name "unconnected-(U5-NC7-Pad7)") (class "Default")
      (node (ref "U5") (pin "7") (pinfunction "NC7_7") (pintype "no_connect"))
    )
    (net (code "55") (name "unconnected-(U6-ALERT-Pad3)") (class "Default")
      (node (ref "U6") (pin "3") (pinfunction "ALERT_3") (pintype "bidirectional"))
    )
    (net (code "56") (name "unconnected-(U7-INT-Pad5)") (class "Default")
      (node (ref "U7") (pin "5") (pinfunction "INT_5") (pintype "output"))
    )
  )
)
